# c65Keyb.net
KiCad netlist of a schematic drawn in EAGLE
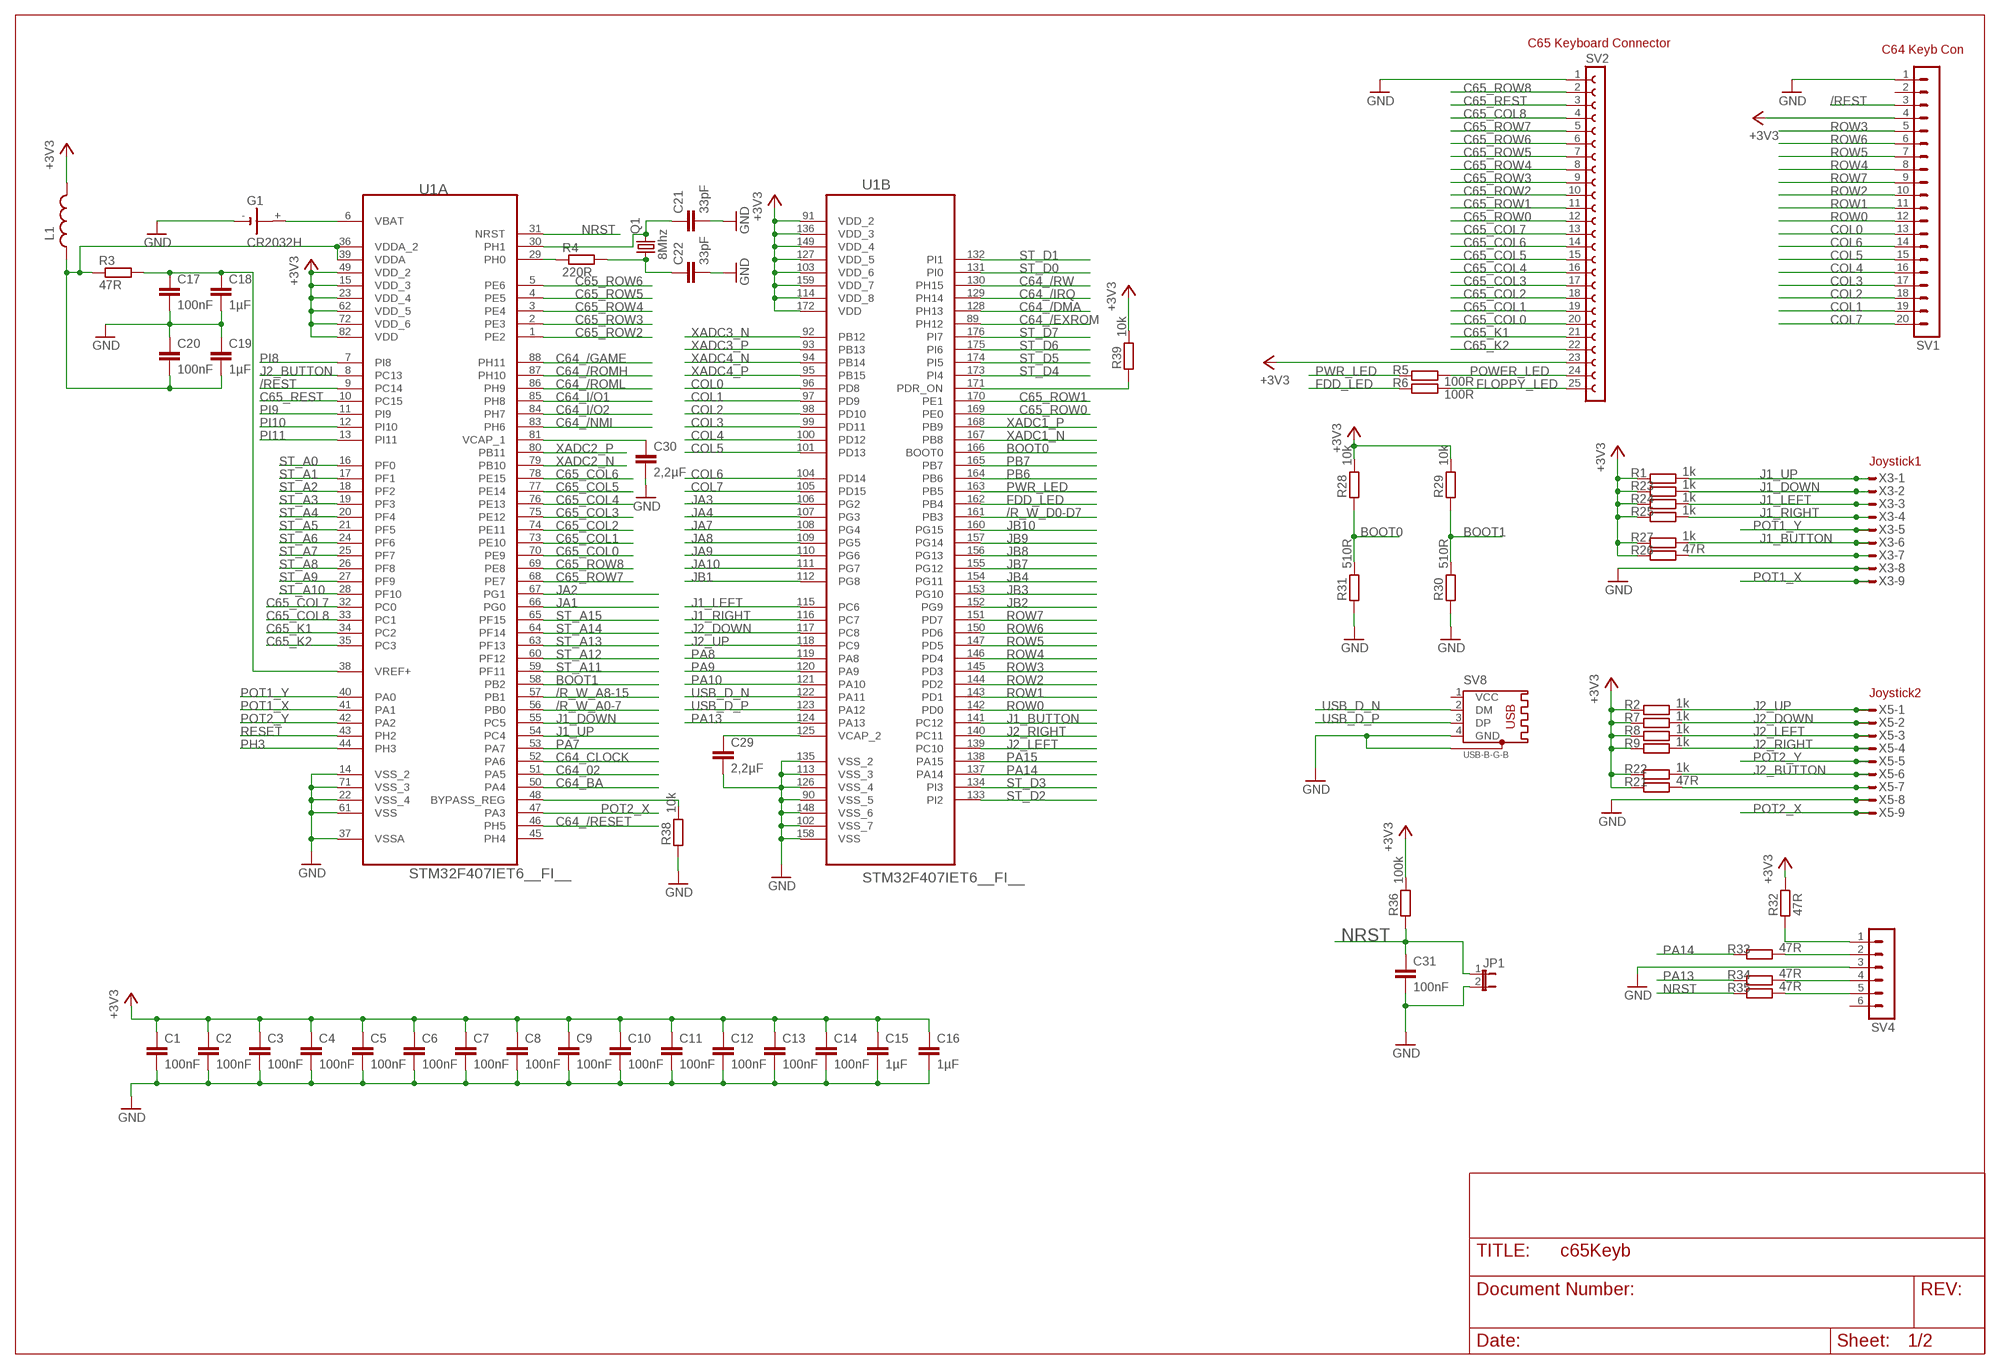
[diagram p0: schematic, sheet 1]
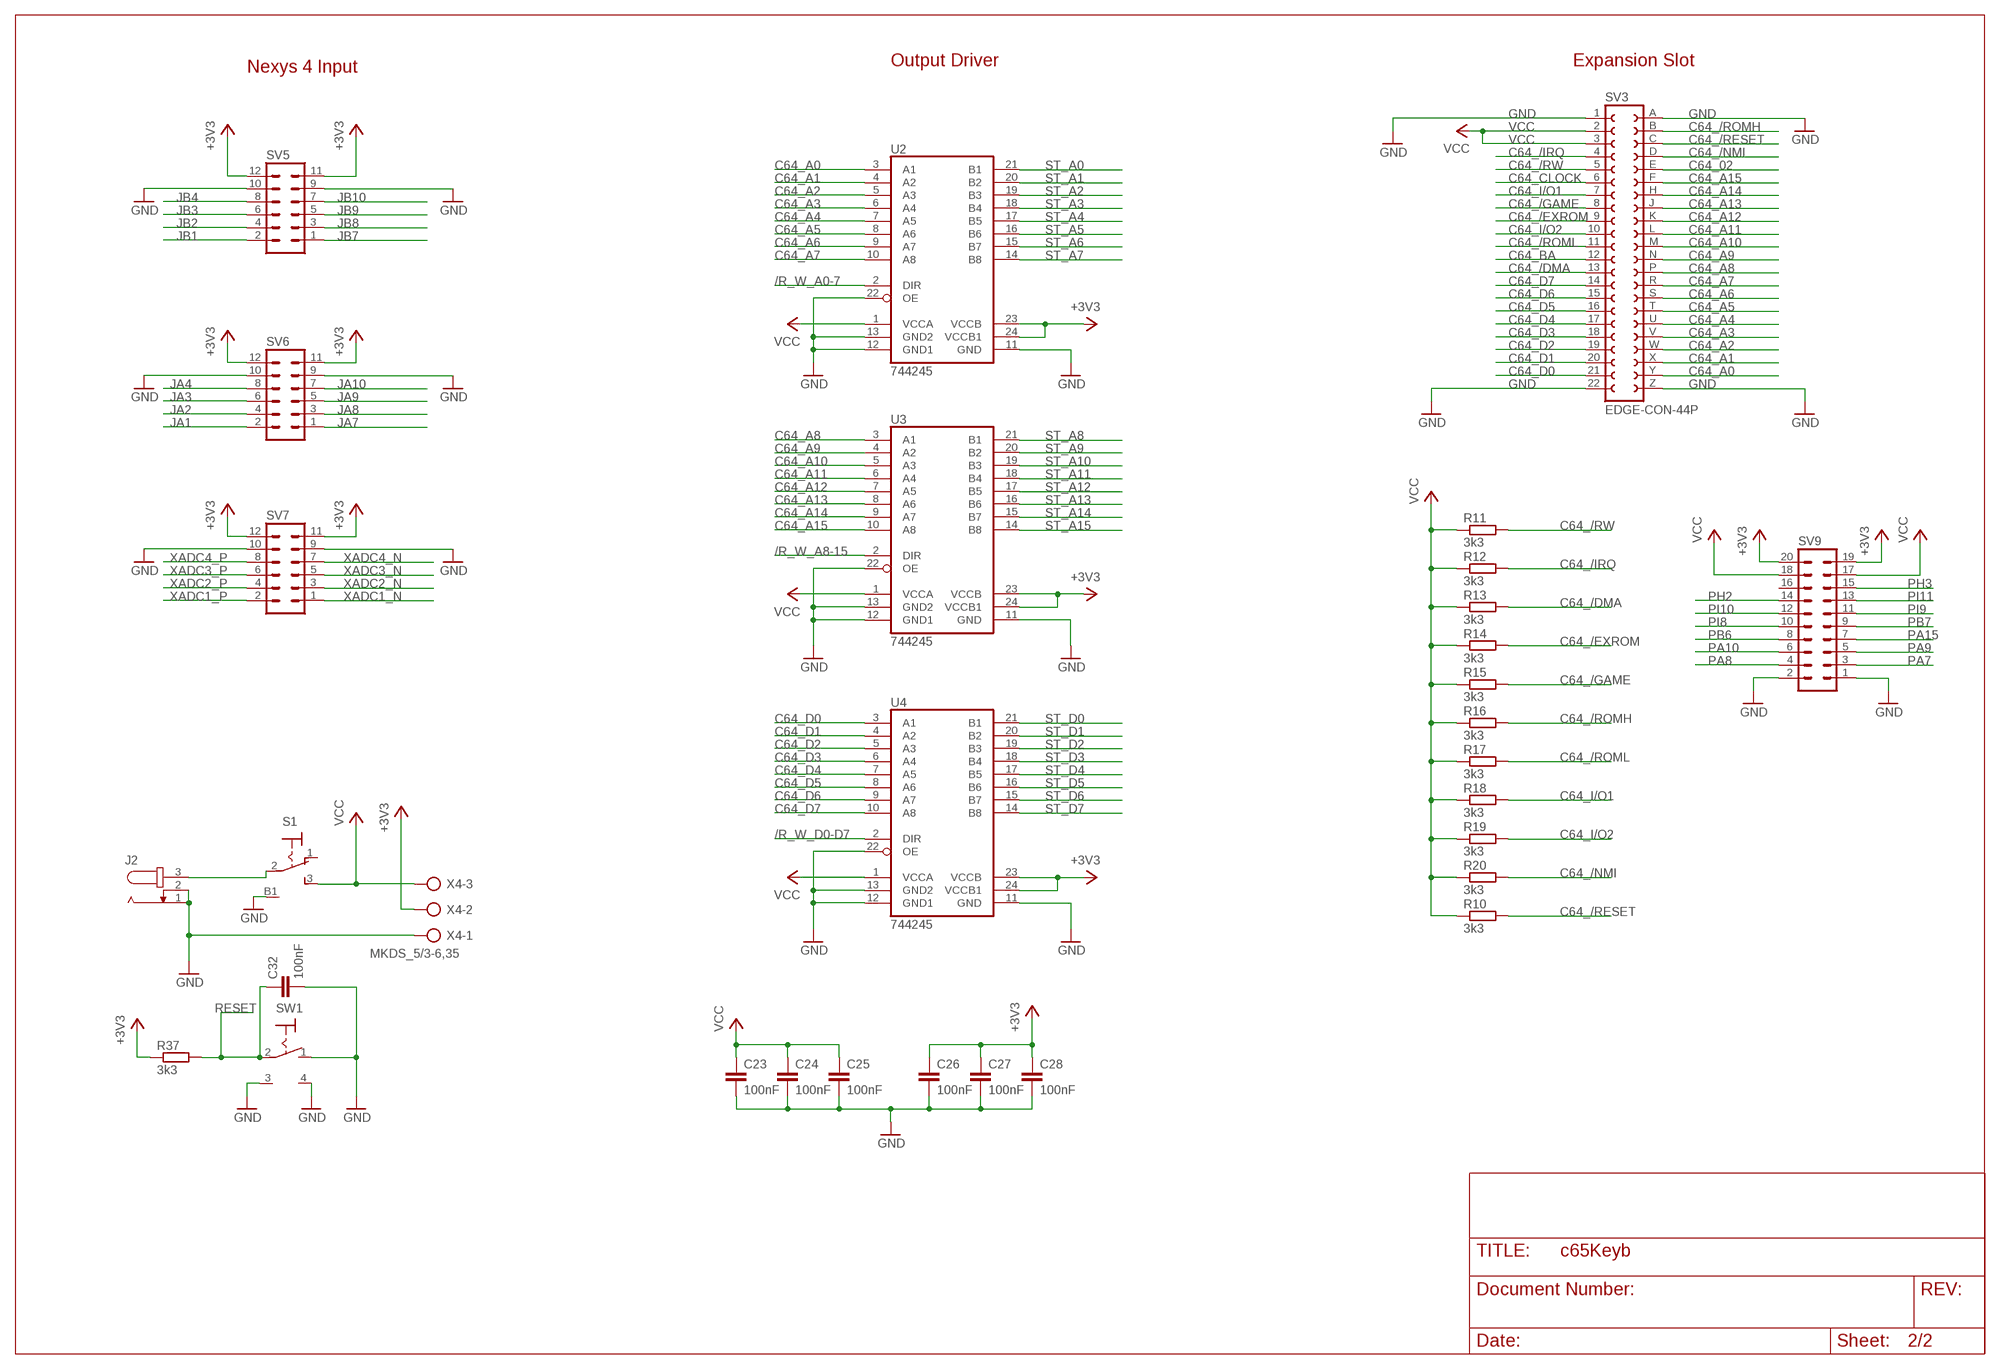
[diagram p1: schematic, sheet 2]

(export (version "E")
  (design (tool "Eeschema 10.0.6"))
  (components
    (comp (ref "C1")
      (value "100nF")
      (footprint "eagle-import:C0805")
      (libsource (lib "eagle-import") (part "C-EUC0805"))
    )
    (comp (ref "C2")
      (value "100nF")
      (footprint "eagle-import:C0805")
      (libsource (lib "eagle-import") (part "C-EUC0805"))
    )
    (comp (ref "C3")
      (value "100nF")
      (footprint "eagle-import:C0805")
      (libsource (lib "eagle-import") (part "C-EUC0805"))
    )
    (comp (ref "C4")
      (value "100nF")
      (footprint "eagle-import:C0805")
      (libsource (lib "eagle-import") (part "C-EUC0805"))
    )
    (comp (ref "C5")
      (value "100nF")
      (footprint "eagle-import:C0805")
      (libsource (lib "eagle-import") (part "C-EUC0805"))
    )
    (comp (ref "C6")
      (value "100nF")
      (footprint "eagle-import:C0805")
      (libsource (lib "eagle-import") (part "C-EUC0805"))
    )
    (comp (ref "C7")
      (value "100nF")
      (footprint "eagle-import:C0805")
      (libsource (lib "eagle-import") (part "C-EUC0805"))
    )
    (comp (ref "C8")
      (value "100nF")
      (footprint "eagle-import:C0805")
      (libsource (lib "eagle-import") (part "C-EUC0805"))
    )
    (comp (ref "C9")
      (value "100nF")
      (footprint "eagle-import:C0805")
      (libsource (lib "eagle-import") (part "C-EUC0805"))
    )
    (comp (ref "C10")
      (value "100nF")
      (footprint "eagle-import:C0805")
      (libsource (lib "eagle-import") (part "C-EUC0805"))
    )
    (comp (ref "C11")
      (value "100nF")
      (footprint "eagle-import:C0805")
      (libsource (lib "eagle-import") (part "C-EUC0805"))
    )
    (comp (ref "C12")
      (value "100nF")
      (footprint "eagle-import:C0805")
      (libsource (lib "eagle-import") (part "C-EUC0805"))
    )
    (comp (ref "C13")
      (value "100nF")
      (footprint "eagle-import:C0805")
      (libsource (lib "eagle-import") (part "C-EUC0805"))
    )
    (comp (ref "C14")
      (value "100nF")
      (footprint "eagle-import:C0805")
      (libsource (lib "eagle-import") (part "C-EUC0805"))
    )
    (comp (ref "C15")
      (value "1µF")
      (footprint "eagle-import:C0805")
      (libsource (lib "eagle-import") (part "C-EUC0805"))
    )
    (comp (ref "C16")
      (value "1µF")
      (footprint "eagle-import:C0805")
      (libsource (lib "eagle-import") (part "C-EUC0805"))
    )
    (comp (ref "C17")
      (value "100nF")
      (footprint "eagle-import:C0805")
      (libsource (lib "eagle-import") (part "C-EUC0805"))
    )
    (comp (ref "C18")
      (value "1µF")
      (footprint "eagle-import:C0805")
      (libsource (lib "eagle-import") (part "C-EUC0805"))
    )
    (comp (ref "C19")
      (value "1µF")
      (footprint "eagle-import:C0805")
      (libsource (lib "eagle-import") (part "C-EUC0805"))
    )
    (comp (ref "C20")
      (value "100nF")
      (footprint "eagle-import:C0805")
      (libsource (lib "eagle-import") (part "C-EUC0805"))
    )
    (comp (ref "C21")
      (value "33pF")
      (footprint "eagle-import:C0805")
      (libsource (lib "eagle-import") (part "C-EUC0805"))
    )
    (comp (ref "C22")
      (value "33pF")
      (footprint "eagle-import:C0805")
      (libsource (lib "eagle-import") (part "C-EUC0805"))
    )
    (comp (ref "C29")
      (value "2,2µF")
      (footprint "eagle-import:C0805")
      (libsource (lib "eagle-import") (part "C-EUC0805"))
    )
    (comp (ref "C30")
      (value "2,2µF")
      (footprint "eagle-import:C0805")
      (libsource (lib "eagle-import") (part "C-EUC0805"))
    )
    (comp (ref "C31")
      (value "100nF")
      (footprint "eagle-import:C0805")
      (libsource (lib "eagle-import") (part "C-EUC0805"))
    )
    (comp (ref "G1")
      (value "CR2032H")
      (footprint "eagle-import:CR2032H")
      (libsource (lib "eagle-import") (part "CR2032H"))
    )
    (comp (ref "JP1")
      (value "JP1E")
      (footprint "eagle-import:JP1")
      (libsource (lib "eagle-import") (part "JP1E"))
    )
    (comp (ref "L1")
      (value "L-0805A")
      (footprint "eagle-import:SMD0805-ALT")
      (libsource (lib "eagle-import") (part "L-0805A"))
    )
    (comp (ref "Q1")
      (value "8Mhz")
      (footprint "eagle-import:HC49UP")
      (libsource (lib "eagle-import") (part "CRYSTAL-HC49UP"))
    )
    (comp (ref "R1")
      (value "1k")
      (footprint "eagle-import:R0805")
      (libsource (lib "eagle-import") (part "R-EU_R0805"))
    )
    (comp (ref "R2")
      (value "1k")
      (footprint "eagle-import:R0805")
      (libsource (lib "eagle-import") (part "R-EU_R0805"))
    )
    (comp (ref "R3")
      (value "47R")
      (footprint "eagle-import:R0805")
      (libsource (lib "eagle-import") (part "R-EU_R0805"))
    )
    (comp (ref "R4")
      (value "220R")
      (footprint "eagle-import:R0805")
      (libsource (lib "eagle-import") (part "R-EU_R0805"))
    )
    (comp (ref "R5")
      (value "100R")
      (footprint "eagle-import:R0805")
      (libsource (lib "eagle-import") (part "R-EU_R0805"))
    )
    (comp (ref "R6")
      (value "100R")
      (footprint "eagle-import:R0805")
      (libsource (lib "eagle-import") (part "R-EU_R0805"))
    )
    (comp (ref "R7")
      (value "1k")
      (footprint "eagle-import:R0805")
      (libsource (lib "eagle-import") (part "R-EU_R0805"))
    )
    (comp (ref "R8")
      (value "1k")
      (footprint "eagle-import:R0805")
      (libsource (lib "eagle-import") (part "R-EU_R0805"))
    )
    (comp (ref "R9")
      (value "1k")
      (footprint "eagle-import:R0805")
      (libsource (lib "eagle-import") (part "R-EU_R0805"))
    )
    (comp (ref "R21")
      (value "47R")
      (footprint "eagle-import:R0805")
      (libsource (lib "eagle-import") (part "R-EU_R0805"))
    )
    (comp (ref "R22")
      (value "1k")
      (footprint "eagle-import:R0805")
      (libsource (lib "eagle-import") (part "R-EU_R0805"))
    )
    (comp (ref "R23")
      (value "1k")
      (footprint "eagle-import:R0805")
      (libsource (lib "eagle-import") (part "R-EU_R0805"))
    )
    (comp (ref "R24")
      (value "1k")
      (footprint "eagle-import:R0805")
      (libsource (lib "eagle-import") (part "R-EU_R0805"))
    )
    (comp (ref "R25")
      (value "1k")
      (footprint "eagle-import:R0805")
      (libsource (lib "eagle-import") (part "R-EU_R0805"))
    )
    (comp (ref "R26")
      (value "47R")
      (footprint "eagle-import:R0805")
      (libsource (lib "eagle-import") (part "R-EU_R0805"))
    )
    (comp (ref "R27")
      (value "1k")
      (footprint "eagle-import:R0805")
      (libsource (lib "eagle-import") (part "R-EU_R0805"))
    )
    (comp (ref "R28")
      (value "10k")
      (footprint "eagle-import:R0805")
      (libsource (lib "eagle-import") (part "R-EU_R0805"))
    )
    (comp (ref "R29")
      (value "10k")
      (footprint "eagle-import:R0805")
      (libsource (lib "eagle-import") (part "R-EU_R0805"))
    )
    (comp (ref "R30")
      (value "510R")
      (footprint "eagle-import:R0805")
      (libsource (lib "eagle-import") (part "R-EU_R0805"))
    )
    (comp (ref "R31")
      (value "510R")
      (footprint "eagle-import:R0805")
      (libsource (lib "eagle-import") (part "R-EU_R0805"))
    )
    (comp (ref "R32")
      (value "47R")
      (footprint "eagle-import:R0805")
      (libsource (lib "eagle-import") (part "R-EU_R0805"))
    )
    (comp (ref "R33")
      (value "47R")
      (footprint "eagle-import:R0805")
      (libsource (lib "eagle-import") (part "R-EU_R0805"))
    )
    (comp (ref "R34")
      (value "47R")
      (footprint "eagle-import:R0805")
      (libsource (lib "eagle-import") (part "R-EU_R0805"))
    )
    (comp (ref "R35")
      (value "47R")
      (footprint "eagle-import:R0805")
      (libsource (lib "eagle-import") (part "R-EU_R0805"))
    )
    (comp (ref "R36")
      (value "100k")
      (footprint "eagle-import:R0805")
      (libsource (lib "eagle-import") (part "R-EU_R0805"))
    )
    (comp (ref "R38")
      (value "10k")
      (footprint "eagle-import:R0805")
      (libsource (lib "eagle-import") (part "R-EU_R0805"))
    )
    (comp (ref "R39")
      (value "10k")
      (footprint "eagle-import:R0805")
      (libsource (lib "eagle-import") (part "R-EU_R0805"))
    )
    (comp (ref "SV1")
      (value "MA20-1")
      (footprint "eagle-import:MA20-1")
      (libsource (lib "eagle-import") (part "MA20-1"))
    )
    (comp (ref "SV2")
      (value "C65_MOLEX_KEYB")
      (footprint "eagle-import:C65_MOLEX_KEYB")
      (libsource (lib "eagle-import") (part "C65_MOLEX_KEYB"))
    )
    (comp (ref "SV4")
      (value "MA06-1")
      (footprint "eagle-import:MA06-1")
      (libsource (lib "eagle-import") (part "MA06-1"))
    )
    (comp (ref "SV8")
      (value "USB-B-G-B")
      (footprint "eagle-import:USB-B-THG-01")
      (libsource (lib "eagle-import") (part "USB-B-G-B"))
    )
    (comp (ref "U1")
      (value "STM32F407IET6__FI__")
      (footprint "eagle-import:QFP176")
      (libsource (lib "eagle-import") (part "STM32F407IET6__FI__"))
    )
    (comp (ref "X3")
      (value "M09-182S")
      (footprint "eagle-import:182-009-MALE")
      (libsource (lib "eagle-import") (part "M09?S-182"))
    )
    (comp (ref "X5")
      (value "M09-182S")
      (footprint "eagle-import:182-009-MALE")
      (libsource (lib "eagle-import") (part "M09?S-182"))
    )
    (comp (ref "C23")
      (value "100nF")
      (footprint "eagle-import:C0805")
      (libsource (lib "eagle-import") (part "C-EUC0805"))
    )
    (comp (ref "C24")
      (value "100nF")
      (footprint "eagle-import:C0805")
      (libsource (lib "eagle-import") (part "C-EUC0805"))
    )
    (comp (ref "C25")
      (value "100nF")
      (footprint "eagle-import:C0805")
      (libsource (lib "eagle-import") (part "C-EUC0805"))
    )
    (comp (ref "C26")
      (value "100nF")
      (footprint "eagle-import:C0805")
      (libsource (lib "eagle-import") (part "C-EUC0805"))
    )
    (comp (ref "C27")
      (value "100nF")
      (footprint "eagle-import:C0805")
      (libsource (lib "eagle-import") (part "C-EUC0805"))
    )
    (comp (ref "C28")
      (value "100nF")
      (footprint "eagle-import:C0805")
      (libsource (lib "eagle-import") (part "C-EUC0805"))
    )
    (comp (ref "C32")
      (value "100nF")
      (footprint "eagle-import:C0805")
      (libsource (lib "eagle-import") (part "C-EUC0805"))
    )
    (comp (ref "J2")
      (value "JACK-PLUG1")
      (footprint "eagle-import:SPC4078")
      (libsource (lib "eagle-import") (part "JACK-PLUG1"))
    )
    (comp (ref "R10")
      (value "3k3")
      (footprint "eagle-import:R0805")
      (libsource (lib "eagle-import") (part "R-EU_R0805"))
    )
    (comp (ref "R11")
      (value "3k3")
      (footprint "eagle-import:R0805")
      (libsource (lib "eagle-import") (part "R-EU_R0805"))
    )
    (comp (ref "R12")
      (value "3k3")
      (footprint "eagle-import:R0805")
      (libsource (lib "eagle-import") (part "R-EU_R0805"))
    )
    (comp (ref "R13")
      (value "3k3")
      (footprint "eagle-import:R0805")
      (libsource (lib "eagle-import") (part "R-EU_R0805"))
    )
    (comp (ref "R14")
      (value "3k3")
      (footprint "eagle-import:R0805")
      (libsource (lib "eagle-import") (part "R-EU_R0805"))
    )
    (comp (ref "R15")
      (value "3k3")
      (footprint "eagle-import:R0805")
      (libsource (lib "eagle-import") (part "R-EU_R0805"))
    )
    (comp (ref "R16")
      (value "3k3")
      (footprint "eagle-import:R0805")
      (libsource (lib "eagle-import") (part "R-EU_R0805"))
    )
    (comp (ref "R17")
      (value "3k3")
      (footprint "eagle-import:R0805")
      (libsource (lib "eagle-import") (part "R-EU_R0805"))
    )
    (comp (ref "R18")
      (value "3k3")
      (footprint "eagle-import:R0805")
      (libsource (lib "eagle-import") (part "R-EU_R0805"))
    )
    (comp (ref "R19")
      (value "3k3")
      (footprint "eagle-import:R0805")
      (libsource (lib "eagle-import") (part "R-EU_R0805"))
    )
    (comp (ref "R20")
      (value "3k3")
      (footprint "eagle-import:R0805")
      (libsource (lib "eagle-import") (part "R-EU_R0805"))
    )
    (comp (ref "R37")
      (value "3k3")
      (footprint "eagle-import:R0805")
      (libsource (lib "eagle-import") (part "R-EU_R0805"))
    )
    (comp (ref "S1")
      (value "LPV-1")
      (footprint "eagle-import:LPV-1")
      (libsource (lib "eagle-import") (part "LPV-1"))
    )
    (comp (ref "SV3")
      (value "EDGE-CON-44P")
      (footprint "eagle-import:EDGE-CON-44")
      (libsource (lib "eagle-import") (part "EDGE-CON-44P"))
    )
    (comp (ref "SV5")
      (value "MA06-2W")
      (footprint "eagle-import:MA06-2W")
      (libsource (lib "eagle-import") (part "MA06-2W"))
    )
    (comp (ref "SV6")
      (value "MA06-2W")
      (footprint "eagle-import:MA06-2W")
      (libsource (lib "eagle-import") (part "MA06-2W"))
    )
    (comp (ref "SV7")
      (value "MA06-2W")
      (footprint "eagle-import:MA06-2W")
      (libsource (lib "eagle-import") (part "MA06-2W"))
    )
    (comp (ref "SV9")
      (value "MA10-2")
      (footprint "eagle-import:MA10-2")
      (libsource (lib "eagle-import") (part "MA10-2"))
    )
    (comp (ref "SW1")
      (value "TASTER")
      (footprint "eagle-import:MICRO_SWITCH")
      (libsource (lib "eagle-import") (part "TASTER"))
    )
    (comp (ref "U2")
      (value "744245")
      (footprint "eagle-import:SO24L")
      (libsource (lib "eagle-import") (part "744245"))
    )
    (comp (ref "U3")
      (value "744245")
      (footprint "eagle-import:SO24L")
      (libsource (lib "eagle-import") (part "744245"))
    )
    (comp (ref "U4")
      (value "744245")
      (footprint "eagle-import:SO24L")
      (libsource (lib "eagle-import") (part "744245"))
    )
    (comp (ref "X4")
      (value "MKDS_5/3-6,35")
      (footprint "eagle-import:MKDS_5_3-635")
      (fields (field (name "MF") "FARNELL") (field (name "MPN") "1714968"))
      (libsource (lib "eagle-import") (part "MKDS_5/3-6,35"))
    )
  )
  (nets
    (net (code "1") (name "+3V3") (class "Default")
      (node (ref "C1") (pin "1") (pinfunction "1_1") (pintype "passive"))
      (node (ref "C10") (pin "1") (pinfunction "1_1") (pintype "passive"))
      (node (ref "C11") (pin "1") (pinfunction "1_1") (pintype "passive"))
      (node (ref "C12") (pin "1") (pinfunction "1_1") (pintype "passive"))
      (node (ref "C13") (pin "1") (pinfunction "1_1") (pintype "passive"))
      (node (ref "C14") (pin "1") (pinfunction "1_1") (pintype "passive"))
      (node (ref "C15") (pin "1") (pinfunction "1_1") (pintype "passive"))
      (node (ref "C16") (pin "1") (pinfunction "1_1") (pintype "passive"))
      (node (ref "C2") (pin "1") (pinfunction "1_1") (pintype "passive"))
      (node (ref "C26") (pin "1") (pinfunction "1_1") (pintype "passive"))
      (node (ref "C27") (pin "1") (pinfunction "1_1") (pintype "passive"))
      (node (ref "C28") (pin "1") (pinfunction "1_1") (pintype "passive"))
      (node (ref "C3") (pin "1") (pinfunction "1_1") (pintype "passive"))
      (node (ref "C4") (pin "1") (pinfunction "1_1") (pintype "passive"))
      (node (ref "C5") (pin "1") (pinfunction "1_1") (pintype "passive"))
      (node (ref "C6") (pin "1") (pinfunction "1_1") (pintype "passive"))
      (node (ref "C7") (pin "1") (pinfunction "1_1") (pintype "passive"))
      (node (ref "C8") (pin "1") (pinfunction "1_1") (pintype "passive"))
      (node (ref "C9") (pin "1") (pinfunction "1_1") (pintype "passive"))
      (node (ref "L1") (pin "2") (pinfunction "2_2") (pintype "passive"))
      (node (ref "R1") (pin "1") (pinfunction "1_1") (pintype "passive"))
      (node (ref "R2") (pin "1") (pinfunction "1_1") (pintype "passive"))
      (node (ref "R21") (pin "1") (pinfunction "1_1") (pintype "passive"))
      (node (ref "R22") (pin "1") (pinfunction "1_1") (pintype "passive"))
      (node (ref "R23") (pin "1") (pinfunction "1_1") (pintype "passive"))
      (node (ref "R24") (pin "1") (pinfunction "1_1") (pintype "passive"))
      (node (ref "R25") (pin "1") (pinfunction "1_1") (pintype "passive"))
      (node (ref "R26") (pin "1") (pinfunction "1_1") (pintype "passive"))
      (node (ref "R27") (pin "1") (pinfunction "1_1") (pintype "passive"))
      (node (ref "R28") (pin "2") (pinfunction "2_2") (pintype "passive"))
      (node (ref "R29") (pin "2") (pinfunction "2_2") (pintype "passive"))
      (node (ref "R32") (pin "2") (pinfunction "2_2") (pintype "passive"))
      (node (ref "R36") (pin "2") (pinfunction "2_2") (pintype "passive"))
      (node (ref "R37") (pin "1") (pinfunction "1_1") (pintype "passive"))
      (node (ref "R39") (pin "2") (pinfunction "2_2") (pintype "passive"))
      (node (ref "R7") (pin "1") (pinfunction "1_1") (pintype "passive"))
      (node (ref "R8") (pin "1") (pinfunction "1_1") (pintype "passive"))
      (node (ref "R9") (pin "1") (pinfunction "1_1") (pintype "passive"))
      (node (ref "SV1") (pin "4") (pinfunction "4_4") (pintype "passive"))
      (node (ref "SV2") (pin "23") (pinfunction "P23_23") (pintype "passive"))
      (node (ref "SV5") (pin "11") (pinfunction "11_11") (pintype "passive"))
      (node (ref "SV5") (pin "12") (pinfunction "12_12") (pintype "passive"))
      (node (ref "SV6") (pin "11") (pinfunction "11_11") (pintype "passive"))
      (node (ref "SV6") (pin "12") (pinfunction "12_12") (pintype "passive"))
      (node (ref "SV7") (pin "11") (pinfunction "11_11") (pintype "passive"))
      (node (ref "SV7") (pin "12") (pinfunction "12_12") (pintype "passive"))
      (node (ref "SV9") (pin "19") (pinfunction "19_19") (pintype "passive"))
      (node (ref "SV9") (pin "20") (pinfunction "20_20") (pintype "passive"))
      (node (ref "U1") (pin "103") (pinfunction "VDD_6_103") (pintype "power_in"))
      (node (ref "U1") (pin "114") (pinfunction "VDD_8_114") (pintype "power_in"))
      (node (ref "U1") (pin "127") (pinfunction "VDD_5_127") (pintype "power_in"))
      (node (ref "U1") (pin "136") (pinfunction "VDD_3_136") (pintype "power_in"))
      (node (ref "U1") (pin "149") (pinfunction "VDD_4_149") (pintype "power_in"))
      (node (ref "U1") (pin "15") (pinfunction "VDD_3_15") (pintype "power_in"))
      (node (ref "U1") (pin "159") (pinfunction "VDD_7_159") (pintype "power_in"))
      (node (ref "U1") (pin "172") (pinfunction "VDD_172") (pintype "power_in"))
      (node (ref "U1") (pin "23") (pinfunction "VDD_4_23") (pintype "power_in"))
      (node (ref "U1") (pin "49") (pinfunction "VDD_2_49") (pintype "power_in"))
      (node (ref "U1") (pin "62") (pinfunction "VDD_5_62") (pintype "power_in"))
      (node (ref "U1") (pin "72") (pinfunction "VDD_6_72") (pintype "power_in"))
      (node (ref "U1") (pin "82") (pinfunction "VDD_82") (pintype "power_in"))
      (node (ref "U1") (pin "91") (pinfunction "VDD_2_91") (pintype "power_in"))
      (node (ref "U2") (pin "23") (pinfunction "VCCB_23") (pintype "power_in"))
      (node (ref "U2") (pin "24") (pinfunction "VCCB1_24") (pintype "power_in"))
      (node (ref "U3") (pin "23") (pinfunction "VCCB_23") (pintype "power_in"))
      (node (ref "U3") (pin "24") (pinfunction "VCCB1_24") (pintype "power_in"))
      (node (ref "U4") (pin "23") (pinfunction "VCCB_23") (pintype "power_in"))
      (node (ref "U4") (pin "24") (pinfunction "VCCB1_24") (pintype "power_in"))
      (node (ref "X4") (pin "2") (pinfunction "KL_2") (pintype "passive"))
    )
    (net (code "2") (name "BOOT0") (class "Default")
      (node (ref "R28") (pin "1") (pinfunction "1_1") (pintype "passive"))
      (node (ref "R31") (pin "2") (pinfunction "2_2") (pintype "passive"))
      (node (ref "U1") (pin "166") (pinfunction "BOOT0_166") (pintype "passive"))
    )
    (net (code "3") (name "BOOT1") (class "Default")
      (node (ref "R29") (pin "1") (pinfunction "1_1") (pintype "passive"))
      (node (ref "R30") (pin "2") (pinfunction "2_2") (pintype "passive"))
      (node (ref "U1") (pin "58") (pinfunction "PB2_58") (pintype "bidirectional"))
    )
    (net (code "4") (name "C64_02") (class "Default")
      (node (ref "SV3") (pin "E") (pinfunction "E_E") (pintype "passive"))
      (node (ref "U1") (pin "51") (pinfunction "PA5_51") (pintype "passive"))
    )
    (net (code "5") (name "C64_A0") (class "Default")
      (node (ref "SV3") (pin "Y") (pinfunction "Y_Y") (pintype "passive"))
      (node (ref "U2") (pin "3") (pinfunction "A1_3") (pintype "bidirectional"))
    )
    (net (code "6") (name "C64_A1") (class "Default")
      (node (ref "SV3") (pin "X") (pinfunction "X_X") (pintype "passive"))
      (node (ref "U2") (pin "4") (pinfunction "A2_4") (pintype "bidirectional"))
    )
    (net (code "7") (name "C64_A2") (class "Default")
      (node (ref "SV3") (pin "W") (pinfunction "W_W") (pintype "passive"))
      (node (ref "U2") (pin "5") (pinfunction "A3_5") (pintype "bidirectional"))
    )
    (net (code "8") (name "C64_A3") (class "Default")
      (node (ref "SV3") (pin "V") (pinfunction "V_V") (pintype "passive"))
      (node (ref "U2") (pin "6") (pinfunction "A4_6") (pintype "bidirectional"))
    )
    (net (code "9") (name "C64_A4") (class "Default")
      (node (ref "SV3") (pin "U") (pinfunction "U_U") (pintype "passive"))
      (node (ref "U2") (pin "7") (pinfunction "A5_7") (pintype "bidirectional"))
    )
    (net (code "10") (name "C64_A5") (class "Default")
      (node (ref "SV3") (pin "T") (pinfunction "T_T") (pintype "passive"))
      (node (ref "U2") (pin "8") (pinfunction "A6_8") (pintype "bidirectional"))
    )
    (net (code "11") (name "C64_A6") (class "Default")
      (node (ref "SV3") (pin "S") (pinfunction "S_S") (pintype "passive"))
      (node (ref "U2") (pin "9") (pinfunction "A7_9") (pintype "bidirectional"))
    )
    (net (code "12") (name "C64_A7") (class "Default")
      (node (ref "SV3") (pin "R") (pinfunction "R_R") (pintype "passive"))
      (node (ref "U2") (pin "10") (pinfunction "A8_10") (pintype "bidirectional"))
    )
    (net (code "13") (name "C64_A8") (class "Default")
      (node (ref "SV3") (pin "P") (pinfunction "P_P") (pintype "passive"))
      (node (ref "U3") (pin "3") (pinfunction "A1_3") (pintype "bidirectional"))
    )
    (net (code "14") (name "C64_A9") (class "Default")
      (node (ref "SV3") (pin "N") (pinfunction "N_N") (pintype "passive"))
      (node (ref "U3") (pin "4") (pinfunction "A2_4") (pintype "bidirectional"))
    )
    (net (code "15") (name "C64_A10") (class "Default")
      (node (ref "SV3") (pin "M") (pinfunction "M_M") (pintype "passive"))
      (node (ref "U3") (pin "5") (pinfunction "A3_5") (pintype "bidirectional"))
    )
    (net (code "16") (name "C64_A11") (class "Default")
      (node (ref "SV3") (pin "L") (pinfunction "L_L") (pintype "passive"))
      (node (ref "U3") (pin "6") (pinfunction "A4_6") (pintype "bidirectional"))
    )
    (net (code "17") (name "C64_A12") (class "Default")
      (node (ref "SV3") (pin "K") (pinfunction "K_K") (pintype "passive"))
      (node (ref "U3") (pin "7") (pinfunction "A5_7") (pintype "bidirectional"))
    )
    (net (code "18") (name "C64_A13") (class "Default")
      (node (ref "SV3") (pin "J") (pinfunction "J_J") (pintype "passive"))
      (node (ref "U3") (pin "8") (pinfunction "A6_8") (pintype "bidirectional"))
    )
    (net (code "19") (name "C64_A14") (class "Default")
      (node (ref "SV3") (pin "H") (pinfunction "H_H") (pintype "passive"))
      (node (ref "U3") (pin "9") (pinfunction "A7_9") (pintype "bidirectional"))
    )
    (net (code "20") (name "C64_A15") (class "Default")
      (node (ref "SV3") (pin "F") (pinfunction "F_F") (pintype "passive"))
      (node (ref "U3") (pin "10") (pinfunction "A8_10") (pintype "bidirectional"))
    )
    (net (code "21") (name "C64_BA") (class "Default")
      (node (ref "SV3") (pin "12") (pinfunction "12_12") (pintype "passive"))
      (node (ref "U1") (pin "50") (pinfunction "PA4_50") (pintype "passive"))
    )
    (net (code "22") (name "C64_CLOCK") (class "Default")
      (node (ref "SV3") (pin "6") (pinfunction "6_6") (pintype "passive"))
      (node (ref "U1") (pin "52") (pinfunction "PA6_52") (pintype "passive"))
    )
    (net (code "23") (name "C64_D0") (class "Default")
      (node (ref "SV3") (pin "21") (pinfunction "21_21") (pintype "passive"))
      (node (ref "U4") (pin "3") (pinfunction "A1_3") (pintype "bidirectional"))
    )
    (net (code "24") (name "C64_D1") (class "Default")
      (node (ref "SV3") (pin "20") (pinfunction "20_20") (pintype "passive"))
      (node (ref "U4") (pin "4") (pinfunction "A2_4") (pintype "bidirectional"))
    )
    (net (code "25") (name "C64_D2") (class "Default")
      (node (ref "SV3") (pin "19") (pinfunction "19_19") (pintype "passive"))
      (node (ref "U4") (pin "5") (pinfunction "A3_5") (pintype "bidirectional"))
    )
    (net (code "26") (name "C64_D3") (class "Default")
      (node (ref "SV3") (pin "18") (pinfunction "18_18") (pintype "passive"))
      (node (ref "U4") (pin "6") (pinfunction "A4_6") (pintype "bidirectional"))
    )
    (net (code "27") (name "C64_D4") (class "Default")
      (node (ref "SV3") (pin "17") (pinfunction "17_17") (pintype "passive"))
      (node (ref "U4") (pin "7") (pinfunction "A5_7") (pintype "bidirectional"))
    )
    (net (code "28") (name "C64_D5") (class "Default")
      (node (ref "SV3") (pin "16") (pinfunction "16_16") (pintype "passive"))
      (node (ref "U4") (pin "8") (pinfunction "A6_8") (pintype "bidirectional"))
    )
    (net (code "29") (name "C64_D6") (class "Default")
      (node (ref "SV3") (pin "15") (pinfunction "15_15") (pintype "passive"))
      (node (ref "U4") (pin "9") (pinfunction "A7_9") (pintype "bidirectional"))
    )
    (net (code "30") (name "C64_D7") (class "Default")
      (node (ref "SV3") (pin "14") (pinfunction "14_14") (pintype "passive"))
      (node (ref "U4") (pin "10") (pinfunction "A8_10") (pintype "bidirectional"))
    )
    (net (code "31") (name "C64_I{slash}O1") (class "Default")
      (node (ref "R18") (pin "2") (pinfunction "2_2") (pintype "passive"))
      (node (ref "SV3") (pin "7") (pinfunction "7_7") (pintype "passive"))
      (node (ref "U1") (pin "85") (pinfunction "PH8_85") (pintype "bidirectional"))
    )
    (net (code "32") (name "C64_I{slash}O2") (class "Default")
      (node (ref "R19") (pin "2") (pinfunction "2_2") (pintype "passive"))
      (node (ref "SV3") (pin "10") (pinfunction "10_10") (pintype "passive"))
      (node (ref "U1") (pin "84") (pinfunction "PH7_84") (pintype "bidirectional"))
    )
    (net (code "33") (name "C64_{slash}DMA") (class "Default")
      (node (ref "R13") (pin "2") (pinfunction "2_2") (pintype "passive"))
      (node (ref "SV3") (pin "13") (pinfunction "13_13") (pintype "passive"))
      (node (ref "U1") (pin "128") (pinfunction "PH13_128") (pintype "bidirectional"))
    )
    (net (code "34") (name "C64_{slash}EXROM") (class "Default")
      (node (ref "R14") (pin "2") (pinfunction "2_2") (pintype "passive"))
      (node (ref "SV3") (pin "9") (pinfunction "9_9") (pintype "passive"))
      (node (ref "U1") (pin "89") (pinfunction "PH12_89") (pintype "bidirectional"))
    )
    (net (code "35") (name "C64_{slash}GAME") (class "Default")
      (node (ref "R15") (pin "2") (pinfunction "2_2") (pintype "passive"))
      (node (ref "SV3") (pin "8") (pinfunction "8_8") (pintype "passive"))
      (node (ref "U1") (pin "88") (pinfunction "PH11_88") (pintype "bidirectional"))
    )
    (net (code "36") (name "C64_{slash}IRQ") (class "Default")
      (node (ref "R12") (pin "2") (pinfunction "2_2") (pintype "passive"))
      (node (ref "SV3") (pin "4") (pinfunction "4_4") (pintype "passive"))
      (node (ref "U1") (pin "129") (pinfunction "PH14_129") (pintype "bidirectional"))
    )
    (net (code "37") (name "C64_{slash}NMI") (class "Default")
      (node (ref "R20") (pin "2") (pinfunction "2_2") (pintype "passive"))
      (node (ref "SV3") (pin "D") (pinfunction "D_D") (pintype "passive"))
      (node (ref "U1") (pin "83") (pinfunction "PH6_83") (pintype "bidirectional"))
    )
    (net (code "38") (name "C64_{slash}RESET") (class "Default")
      (node (ref "R10") (pin "2") (pinfunction "2_2") (pintype "passive"))
      (node (ref "SV3") (pin "C") (pinfunction "C_C") (pintype "passive"))
      (node (ref "U1") (pin "46") (pinfunction "PH5_46") (pintype "passive"))
    )
    (net (code "39") (name "C64_{slash}ROMH") (class "Default")
      (node (ref "R16") (pin "2") (pinfunction "2_2") (pintype "passive"))
      (node (ref "SV3") (pin "B") (pinfunction "B_B") (pintype "passive"))
      (node (ref "U1") (pin "87") (pinfunction "PH10_87") (pintype "bidirectional"))
    )
    (net (code "40") (name "C64_{slash}ROML") (class "Default")
      (node (ref "R17") (pin "2") (pinfunction "2_2") (pintype "passive"))
      (node (ref "SV3") (pin "11") (pinfunction "11_11") (pintype "passive"))
      (node (ref "U1") (pin "86") (pinfunction "PH9_86") (pintype "bidirectional"))
    )
    (net (code "41") (name "C64_{slash}RW") (class "Default")
      (node (ref "R11") (pin "2") (pinfunction "2_2") (pintype "passive"))
      (node (ref "SV3") (pin "5") (pinfunction "5_5") (pintype "passive"))
      (node (ref "U1") (pin "130") (pinfunction "PH15_130") (pintype "bidirectional"))
    )
    (net (code "42") (name "C65_COL0") (class "Default")
      (node (ref "SV2") (pin "20") (pinfunction "P20_20") (pintype "passive"))
      (node (ref "U1") (pin "70") (pinfunction "PE9_70") (pintype "bidirectional"))
    )
    (net (code "43") (name "C65_COL1") (class "Default")
      (node (ref "SV2") (pin "19") (pinfunction "P19_19") (pintype "passive"))
      (node (ref "U1") (pin "73") (pinfunction "PE10_73") (pintype "bidirectional"))
    )
    (net (code "44") (name "C65_COL2") (class "Default")
      (node (ref "SV2") (pin "18") (pinfunction "P18_18") (pintype "passive"))
      (node (ref "U1") (pin "74") (pinfunction "PE11_74") (pintype "bidirectional"))
    )
    (net (code "45") (name "C65_COL3") (class "Default")
      (node (ref "SV2") (pin "17") (pinfunction "P17_17") (pintype "passive"))
      (node (ref "U1") (pin "75") (pinfunction "PE12_75") (pintype "bidirectional"))
    )
    (net (code "46") (name "C65_COL4") (class "Default")
      (node (ref "SV2") (pin "16") (pinfunction "P16_16") (pintype "passive"))
      (node (ref "U1") (pin "76") (pinfunction "PE13_76") (pintype "bidirectional"))
    )
    (net (code "47") (name "C65_COL5") (class "Default")
      (node (ref "SV2") (pin "15") (pinfunction "P15_15") (pintype "passive"))
      (node (ref "U1") (pin "77") (pinfunction "PE14_77") (pintype "bidirectional"))
    )
    (net (code "48") (name "C65_COL6") (class "Default")
      (node (ref "SV2") (pin "14") (pinfunction "P14_14") (pintype "passive"))
      (node (ref "U1") (pin "78") (pinfunction "PE15_78") (pintype "bidirectional"))
    )
    (net (code "49") (name "C65_COL7") (class "Default")
      (node (ref "SV2") (pin "13") (pinfunction "P13_13") (pintype "passive"))
      (node (ref "U1") (pin "32") (pinfunction "PC0_32") (pintype "passive"))
    )
    (net (code "50") (name "C65_COL8") (class "Default")
      (node (ref "SV2") (pin "4") (pinfunction "P4_4") (pintype "passive"))
      (node (ref "U1") (pin "33") (pinfunction "PC1_33") (pintype "passive"))
    )
    (net (code "51") (name "C65_K1") (class "Default")
      (node (ref "SV2") (pin "21") (pinfunction "P21_21") (pintype "passive"))
      (node (ref "U1") (pin "34") (pinfunction "PC2_34") (pintype "passive"))
    )
    (net (code "52") (name "C65_K2") (class "Default")
      (node (ref "SV2") (pin "22") (pinfunction "P22_22") (pintype "passive"))
      (node (ref "U1") (pin "35") (pinfunction "PC3_35") (pintype "passive"))
    )
    (net (code "53") (name "C65_REST") (class "Default")
      (node (ref "SV2") (pin "3") (pinfunction "P3_3") (pintype "passive"))
      (node (ref "U1") (pin "10") (pinfunction "PC15_10") (pintype "passive"))
    )
    (net (code "54") (name "C65_ROW0") (class "Default")
      (node (ref "SV2") (pin "12") (pinfunction "P12_12") (pintype "passive"))
      (node (ref "U1") (pin "169") (pinfunction "PE0_169") (pintype "bidirectional"))
    )
    (net (code "55") (name "C65_ROW1") (class "Default")
      (node (ref "SV2") (pin "11") (pinfunction "P11_11") (pintype "passive"))
      (node (ref "U1") (pin "170") (pinfunction "PE1_170") (pintype "bidirectional"))
    )
    (net (code "56") (name "C65_ROW2") (class "Default")
      (node (ref "SV2") (pin "10") (pinfunction "P10_10") (pintype "passive"))
      (node (ref "U1") (pin "1") (pinfunction "PE2_1") (pintype "passive"))
    )
    (net (code "57") (name "C65_ROW3") (class "Default")
      (node (ref "SV2") (pin "9") (pinfunction "P9_9") (pintype "passive"))
      (node (ref "U1") (pin "2") (pinfunction "PE3_2") (pintype "passive"))
    )
    (net (code "58") (name "C65_ROW4") (class "Default")
      (node (ref "SV2") (pin "8") (pinfunction "P8_8") (pintype "passive"))
      (node (ref "U1") (pin "3") (pinfunction "PE4_3") (pintype "passive"))
    )
    (net (code "59") (name "C65_ROW5") (class "Default")
      (node (ref "SV2") (pin "7") (pinfunction "P7_7") (pintype "passive"))
      (node (ref "U1") (pin "4") (pinfunction "PE5_4") (pintype "passive"))
    )
    (net (code "60") (name "C65_ROW6") (class "Default")
      (node (ref "SV2") (pin "6") (pinfunction "P6_6") (pintype "passive"))
      (node (ref "U1") (pin "5") (pinfunction "PE6_5") (pintype "passive"))
    )
    (net (code "61") (name "C65_ROW7") (class "Default")
      (node (ref "SV2") (pin "5") (pinfunction "P5_5") (pintype "passive"))
      (node (ref "U1") (pin "68") (pinfunction "PE7_68") (pintype "bidirectional"))
    )
    (net (code "62") (name "C65_ROW8") (class "Default")
      (node (ref "SV2") (pin "2") (pinfunction "P2_2") (pintype "passive"))
      (node (ref "U1") (pin "69") (pinfunction "PE8_69") (pintype "bidirectional"))
    )
    (net (code "63") (name "COL0") (class "Default")
      (node (ref "SV1") (pin "13") (pinfunction "13_13") (pintype "passive"))
      (node (ref "U1") (pin "96") (pinfunction "PD8_96") (pintype "bidirectional"))
    )
    (net (code "64") (name "COL1") (class "Default")
      (node (ref "SV1") (pin "19") (pinfunction "19_19") (pintype "passive"))
      (node (ref "U1") (pin "97") (pinfunction "PD9_97") (pintype "bidirectional"))
    )
    (net (code "65") (name "COL2") (class "Default")
      (node (ref "SV1") (pin "18") (pinfunction "18_18") (pintype "passive"))
      (node (ref "U1") (pin "98") (pinfunction "PD10_98") (pintype "bidirectional"))
    )
    (net (code "66") (name "COL3") (class "Default")
      (node (ref "SV1") (pin "17") (pinfunction "17_17") (pintype "passive"))
      (node (ref "U1") (pin "99") (pinfunction "PD11_99") (pintype "bidirectional"))
    )
    (net (code "67") (name "COL4") (class "Default")
      (node (ref "SV1") (pin "16") (pinfunction "16_16") (pintype "passive"))
      (node (ref "U1") (pin "100") (pinfunction "PD12_100") (pintype "bidirectional"))
    )
    (net (code "68") (name "COL5") (class "Default")
      (node (ref "SV1") (pin "15") (pinfunction "15_15") (pintype "passive"))
      (node (ref "U1") (pin "101") (pinfunction "PD13_101") (pintype "bidirectional"))
    )
    (net (code "69") (name "COL6") (class "Default")
      (node (ref "SV1") (pin "14") (pinfunction "14_14") (pintype "passive"))
      (node (ref "U1") (pin "104") (pinfunction "PD14_104") (pintype "bidirectional"))
    )
    (net (code "70") (name "COL7") (class "Default")
      (node (ref "SV1") (pin "20") (pinfunction "20_20") (pintype "passive"))
      (node (ref "U1") (pin "105") (pinfunction "PD15_105") (pintype "bidirectional"))
    )
    (net (code "71") (name "FDD_LED") (class "Default")
      (node (ref "R6") (pin "1") (pinfunction "1_1") (pintype "passive"))
      (node (ref "U1") (pin "162") (pinfunction "PB4_162") (pintype "bidirectional"))
    )
    (net (code "72") (name "FLOPPY_LED") (class "Default")
      (node (ref "R6") (pin "2") (pinfunction "2_2") (pintype "passive"))
      (node (ref "SV2") (pin "25") (pinfunction "P25_25") (pintype "passive"))
    )
    (net (code "73") (name "GND") (class "Default")
      (node (ref "C1") (pin "2") (pinfunction "2_2") (pintype "passive"))
      (node (ref "C10") (pin "2") (pinfunction "2_2") (pintype "passive"))
      (node (ref "C11") (pin "2") (pinfunction "2_2") (pintype "passive"))
      (node (ref "C12") (pin "2") (pinfunction "2_2") (pintype "passive"))
      (node (ref "C13") (pin "2") (pinfunction "2_2") (pintype "passive"))
      (node (ref "C14") (pin "2") (pinfunction "2_2") (pintype "passive"))
      (node (ref "C15") (pin "2") (pinfunction "2_2") (pintype "passive"))
      (node (ref "C16") (pin "2") (pinfunction "2_2") (pintype "passive"))
      (node (ref "C17") (pin "2") (pinfunction "2_2") (pintype "passive"))
      (node (ref "C18") (pin "2") (pinfunction "2_2") (pintype "passive"))
      (node (ref "C19") (pin "1") (pinfunction "1_1") (pintype "passive"))
      (node (ref "C2") (pin "2") (pinfunction "2_2") (pintype "passive"))
      (node (ref "C20") (pin "1") (pinfunction "1_1") (pintype "passive"))
      (node (ref "C21") (pin "2") (pinfunction "2_2") (pintype "passive"))
      (node (ref "C22") (pin "2") (pinfunction "2_2") (pintype "passive"))
      (node (ref "C23") (pin "2") (pinfunction "2_2") (pintype "passive"))
      (node (ref "C24") (pin "2") (pinfunction "2_2") (pintype "passive"))
      (node (ref "C25") (pin "2") (pinfunction "2_2") (pintype "passive"))
      (node (ref "C26") (pin "2") (pinfunction "2_2") (pintype "passive"))
      (node (ref "C27") (pin "2") (pinfunction "2_2") (pintype "passive"))
      (node (ref "C28") (pin "2") (pinfunction "2_2") (pintype "passive"))
      (node (ref "C29") (pin "2") (pinfunction "2_2") (pintype "passive"))
      (node (ref "C3") (pin "2") (pinfunction "2_2") (pintype "passive"))
      (node (ref "C30") (pin "2") (pinfunction "2_2") (pintype "passive"))
      (node (ref "C31") (pin "2") (pinfunction "2_2") (pintype "passive"))
      (node (ref "C32") (pin "2") (pinfunction "2_2") (pintype "passive"))
      (node (ref "C4") (pin "2") (pinfunction "2_2") (pintype "passive"))
      (node (ref "C5") (pin "2") (pinfunction "2_2") (pintype "passive"))
      (node (ref "C6") (pin "2") (pinfunction "2_2") (pintype "passive"))
      (node (ref "C7") (pin "2") (pinfunction "2_2") (pintype "passive"))
      (node (ref "C8") (pin "2") (pinfunction "2_2") (pintype "passive"))
      (node (ref "C9") (pin "2") (pinfunction "2_2") (pintype "passive"))
      (node (ref "G1") (pin "-") (pinfunction "-_-") (pintype "passive"))
      (node (ref "J2") (pin "1") (pinfunction "1_1") (pintype "passive"))
      (node (ref "J2") (pin "2") (pinfunction "2_2") (pintype "passive"))
      (node (ref "JP1") (pin "2") (pinfunction "2_2") (pintype "passive"))
      (node (ref "R30") (pin "1") (pinfunction "1_1") (pintype "passive"))
      (node (ref "R31") (pin "1") (pinfunction "1_1") (pintype "passive"))
      (node (ref "R38") (pin "1") (pinfunction "1_1") (pintype "passive"))
      (node (ref "S1") (pin "B1") (pinfunction "B_B1") (pintype "passive"))
      (node (ref "SV1") (pin "1") (pinfunction "1_1") (pintype "passive"))
      (node (ref "SV2") (pin "1") (pinfunction "P1_1") (pintype "passive"))
      (node (ref "SV3") (pin "1") (pinfunction "1_1") (pintype "passive"))
      (node (ref "SV3") (pin "22") (pinfunction "22_22") (pintype "passive"))
      (node (ref "SV3") (pin "A") (pinfunction "A_A") (pintype "passive"))
      (node (ref "SV3") (pin "Z") (pinfunction "Z_Z") (pintype "passive"))
      (node (ref "SV4") (pin "3") (pinfunction "3_3") (pintype "passive"))
      (node (ref "SV5") (pin "10") (pinfunction "10_10") (pintype "passive"))
      (node (ref "SV5") (pin "9") (pinfunction "9_9") (pintype "passive"))
      (node (ref "SV6") (pin "10") (pinfunction "10_10") (pintype "passive"))
      (node (ref "SV6") (pin "9") (pinfunction "9_9") (pintype "passive"))
      (node (ref "SV7") (pin "10") (pinfunction "10_10") (pintype "passive"))
      (node (ref "SV7") (pin "9") (pinfunction "9_9") (pintype "passive"))
      (node (ref "SV8") (pin "4") (pinfunction "GND_4") (pintype "passive"))
      (node (ref "SV8") (pin "G1") (pinfunction "G1_G1") (pintype "passive"))
      (node (ref "SV9") (pin "1") (pinfunction "1_1") (pintype "passive"))
      (node (ref "SV9") (pin "2") (pinfunction "2_2") (pintype "passive"))
      (node (ref "SW1") (pin "1") (pinfunction "O_1") (pintype "passive"))
      (node (ref "SW1") (pin "3") (pinfunction "B_3") (pintype "passive"))
      (node (ref "SW1") (pin "4") (pinfunction "B1_4") (pintype "passive"))
      (node (ref "U1") (pin "102") (pinfunction "VSS_7_102") (pintype "power_in"))
      (node (ref "U1") (pin "113") (pinfunction "VSS_3_113") (pintype "power_in"))
      (node (ref "U1") (pin "126") (pinfunction "VSS_4_126") (pintype "power_in"))
      (node (ref "U1") (pin "135") (pinfunction "VSS_2_135") (pintype "power_in"))
      (node (ref "U1") (pin "14") (pinfunction "VSS_2_14") (pintype "power_in"))
      (node (ref "U1") (pin "148") (pinfunction "VSS_6_148") (pintype "power_in"))
      (node (ref "U1") (pin "158") (pinfunction "VSS_158") (pintype "power_in"))
      (node (ref "U1") (pin "22") (pinfunction "VSS_4_22") (pintype "power_in"))
      (node (ref "U1") (pin "37") (pinfunction "VSSA_37") (pintype "power_in"))
      (node (ref "U1") (pin "61") (pinfunction "VSS_61") (pintype "power_in"))
      (node (ref "U1") (pin "71") (pinfunction "VSS_3_71") (pintype "power_in"))
      (node (ref "U1") (pin "90") (pinfunction "VSS_5_90") (pintype "power_in"))
      (node (ref "U2") (pin "11") (pinfunction "GND_11") (pintype "power_in"))
      (node (ref "U2") (pin "12") (pinfunction "GND1_12") (pintype "power_in"))
      (node (ref "U2") (pin "13") (pinfunction "GND2_13") (pintype "power_in"))
      (node (ref "U2") (pin "22") (pinfunction "OE_22") (pintype "input"))
      (node (ref "U3") (pin "11") (pinfunction "GND_11") (pintype "power_in"))
      (node (ref "U3") (pin "12") (pinfunction "GND1_12") (pintype "power_in"))
      (node (ref "U3") (pin "13") (pinfunction "GND2_13") (pintype "power_in"))
      (node (ref "U3") (pin "22") (pinfunction "OE_22") (pintype "input"))
      (node (ref "U4") (pin "11") (pinfunction "GND_11") (pintype "power_in"))
      (node (ref "U4") (pin "12") (pinfunction "GND1_12") (pintype "power_in"))
      (node (ref "U4") (pin "13") (pinfunction "GND2_13") (pintype "power_in"))
      (node (ref "U4") (pin "22") (pinfunction "OE_22") (pintype "input"))
      (node (ref "X3") (pin "8") (pinfunction "M_8") (pintype "passive"))
      (node (ref "X4") (pin "1") (pinfunction "KL_1") (pintype "passive"))
      (node (ref "X5") (pin "8") (pinfunction "M_8") (pintype "passive"))
    )
    (net (code "74") (name "J1_BUTTON") (class "Default")
      (node (ref "R27") (pin "2") (pinfunction "2_2") (pintype "passive"))
      (node (ref "U1") (pin "141") (pinfunction "PC12_141") (pintype "bidirectional"))
      (node (ref "X3") (pin "6") (pinfunction "M_6") (pintype "passive"))
    )
    (net (code "75") (name "J1_DOWN") (class "Default")
      (node (ref "R23") (pin "2") (pinfunction "2_2") (pintype "passive"))
      (node (ref "U1") (pin "55") (pinfunction "PC5_55") (pintype "bidirectional"))
      (node (ref "X3") (pin "2") (pinfunction "M_2") (pintype "passive"))
    )
    (net (code "76") (name "J1_LEFT") (class "Default")
      (node (ref "R24") (pin "2") (pinfunction "2_2") (pintype "passive"))
      (node (ref "U1") (pin "115") (pinfunction "PC6_115") (pintype "bidirectional"))
      (node (ref "X3") (pin "3") (pinfunction "M_3") (pintype "passive"))
    )
    (net (code "77") (name "J1_RIGHT") (class "Default")
      (node (ref "R25") (pin "2") (pinfunction "2_2") (pintype "passive"))
      (node (ref "U1") (pin "116") (pinfunction "PC7_116") (pintype "bidirectional"))
      (node (ref "X3") (pin "4") (pinfunction "M_4") (pintype "passive"))
    )
    (net (code "78") (name "J1_UP") (class "Default")
      (node (ref "R1") (pin "2") (pinfunction "2_2") (pintype "passive"))
      (node (ref "U1") (pin "54") (pinfunction "PC4_54") (pintype "passive"))
      (node (ref "X3") (pin "1") (pinfunction "M_1") (pintype "passive"))
    )
    (net (code "79") (name "J2_BUTTON") (class "Default")
      (node (ref "R22") (pin "2") (pinfunction "2_2") (pintype "passive"))
      (node (ref "U1") (pin "8") (pinfunction "PC13_8") (pintype "passive"))
      (node (ref "X5") (pin "6") (pinfunction "M_6") (pintype "passive"))
    )
    (net (code "80") (name "J2_DOWN") (class "Default")
      (node (ref "R7") (pin "2") (pinfunction "2_2") (pintype "passive"))
      (node (ref "U1") (pin "117") (pinfunction "PC8_117") (pintype "bidirectional"))
      (node (ref "X5") (pin "2") (pinfunction "M_2") (pintype "passive"))
    )
    (net (code "81") (name "J2_LEFT") (class "Default")
      (node (ref "R8") (pin "2") (pinfunction "2_2") (pintype "passive"))
      (node (ref "U1") (pin "139") (pinfunction "PC10_139") (pintype "bidirectional"))
      (node (ref "X5") (pin "3") (pinfunction "M_3") (pintype "passive"))
    )
    (net (code "82") (name "J2_RIGHT") (class "Default")
      (node (ref "R9") (pin "2") (pinfunction "2_2") (pintype "passive"))
      (node (ref "U1") (pin "140") (pinfunction "PC11_140") (pintype "bidirectional"))
      (node (ref "X5") (pin "4") (pinfunction "M_4") (pintype "passive"))
    )
    (net (code "83") (name "J2_UP") (class "Default")
      (node (ref "R2") (pin "2") (pinfunction "2_2") (pintype "passive"))
      (node (ref "U1") (pin "118") (pinfunction "PC9_118") (pintype "bidirectional"))
      (node (ref "X5") (pin "1") (pinfunction "M_1") (pintype "passive"))
    )
    (net (code "84") (name "JA1") (class "Default")
      (node (ref "SV6") (pin "2") (pinfunction "2_2") (pintype "passive"))
      (node (ref "U1") (pin "66") (pinfunction "PG0_66") (pintype "bidirectional"))
    )
    (net (code "85") (name "JA2") (class "Default")
      (node (ref "SV6") (pin "4") (pinfunction "4_4") (pintype "passive"))
      (node (ref "U1") (pin "67") (pinfunction "PG1_67") (pintype "bidirectional"))
    )
    (net (code "86") (name "JA3") (class "Default")
      (node (ref "SV6") (pin "6") (pinfunction "6_6") (pintype "passive"))
      (node (ref "U1") (pin "106") (pinfunction "PG2_106") (pintype "bidirectional"))
    )
    (net (code "87") (name "JA4") (class "Default")
      (node (ref "SV6") (pin "8") (pinfunction "8_8") (pintype "passive"))
      (node (ref "U1") (pin "107") (pinfunction "PG3_107") (pintype "bidirectional"))
    )
    (net (code "88") (name "JA7") (class "Default")
      (node (ref "SV6") (pin "1") (pinfunction "1_1") (pintype "passive"))
      (node (ref "U1") (pin "108") (pinfunction "PG4_108") (pintype "bidirectional"))
    )
    (net (code "89") (name "JA8") (class "Default")
      (node (ref "SV6") (pin "3") (pinfunction "3_3") (pintype "passive"))
      (node (ref "U1") (pin "109") (pinfunction "PG5_109") (pintype "bidirectional"))
    )
    (net (code "90") (name "JA9") (class "Default")
      (node (ref "SV6") (pin "5") (pinfunction "5_5") (pintype "passive"))
      (node (ref "U1") (pin "110") (pinfunction "PG6_110") (pintype "bidirectional"))
    )
    (net (code "91") (name "JA10") (class "Default")
      (node (ref "SV6") (pin "7") (pinfunction "7_7") (pintype "passive"))
      (node (ref "U1") (pin "111") (pinfunction "PG7_111") (pintype "bidirectional"))
    )
    (net (code "92") (name "JB1") (class "Default")
      (node (ref "SV5") (pin "2") (pinfunction "2_2") (pintype "passive"))
      (node (ref "U1") (pin "112") (pinfunction "PG8_112") (pintype "bidirectional"))
    )
    (net (code "93") (name "JB2") (class "Default")
      (node (ref "SV5") (pin "4") (pinfunction "4_4") (pintype "passive"))
      (node (ref "U1") (pin "152") (pinfunction "PG9_152") (pintype "bidirectional"))
    )
    (net (code "94") (name "JB3") (class "Default")
      (node (ref "SV5") (pin "6") (pinfunction "6_6") (pintype "passive"))
      (node (ref "U1") (pin "153") (pinfunction "PG10_153") (pintype "bidirectional"))
    )
    (net (code "95") (name "JB4") (class "Default")
      (node (ref "SV5") (pin "8") (pinfunction "8_8") (pintype "passive"))
      (node (ref "U1") (pin "154") (pinfunction "PG11_154") (pintype "bidirectional"))
    )
    (net (code "96") (name "JB7") (class "Default")
      (node (ref "SV5") (pin "1") (pinfunction "1_1") (pintype "passive"))
      (node (ref "U1") (pin "155") (pinfunction "PG12_155") (pintype "bidirectional"))
    )
    (net (code "97") (name "JB8") (class "Default")
      (node (ref "SV5") (pin "3") (pinfunction "3_3") (pintype "passive"))
      (node (ref "U1") (pin "156") (pinfunction "PG13_156") (pintype "bidirectional"))
    )
    (net (code "98") (name "JB9") (class "Default")
      (node (ref "SV5") (pin "5") (pinfunction "5_5") (pintype "passive"))
      (node (ref "U1") (pin "157") (pinfunction "PG14_157") (pintype "bidirectional"))
    )
    (net (code "99") (name "JB10") (class "Default")
      (node (ref "SV5") (pin "7") (pinfunction "7_7") (pintype "passive"))
      (node (ref "U1") (pin "160") (pinfunction "PG15_160") (pintype "bidirectional"))
    )
    (net (code "100") (name "NRST") (class "Default")
      (node (ref "C31") (pin "1") (pinfunction "1_1") (pintype "passive"))
      (node (ref "JP1") (pin "1") (pinfunction "1_1") (pintype "passive"))
      (node (ref "R35") (pin "1") (pinfunction "1_1") (pintype "passive"))
      (node (ref "R36") (pin "1") (pinfunction "1_1") (pintype "passive"))
      (node (ref "U1") (pin "31") (pinfunction "NRST_31") (pintype "passive"))
    )
    (net (code "101") (name "Net-(C22-Pad1)") (class "Default")
      (node (ref "C22") (pin "1") (pinfunction "1_1") (pintype "passive"))
      (node (ref "Q1") (pin "1") (pinfunction "1_1") (pintype "passive"))
      (node (ref "R4") (pin "2") (pinfunction "2_2") (pintype "passive"))
    )
    (net (code "102") (name "Net-(R32-Pad1)") (class "Default")
      (node (ref "R32") (pin "1") (pinfunction "1_1") (pintype "passive"))
      (node (ref "SV4") (pin "1") (pinfunction "1_1") (pintype "passive"))
    )
    (net (code "103") (name "Net-(R33-Pad2)") (class "Default")
      (node (ref "R33") (pin "2") (pinfunction "2_2") (pintype "passive"))
      (node (ref "SV4") (pin "2") (pinfunction "2_2") (pintype "passive"))
    )
    (net (code "104") (name "Net-(R34-Pad2)") (class "Default")
      (node (ref "R34") (pin "2") (pinfunction "2_2") (pintype "passive"))
      (node (ref "SV4") (pin "4") (pinfunction "4_4") (pintype "passive"))
    )
    (net (code "105") (name "Net-(R35-Pad2)") (class "Default")
      (node (ref "R35") (pin "2") (pinfunction "2_2") (pintype "passive"))
      (node (ref "SV4") (pin "5") (pinfunction "5_5") (pintype "passive"))
    )
    (net (code "106") (name "Net-(S1-P)") (class "Default")
      (node (ref "J2") (pin "3") (pinfunction "3_3") (pintype "passive"))
      (node (ref "S1") (pin "2") (pinfunction "P_2") (pintype "passive"))
    )
    (net (code "107") (name "Net-(U1A-BYPASS_REG)") (class "Default")
      (node (ref "R38") (pin "2") (pinfunction "2_2") (pintype "passive"))
      (node (ref "U1") (pin "48") (pinfunction "BYPASS_REG_48") (pintype "passive"))
    )
    (net (code "108") (name "Net-(U1A-PH0)") (class "Default")
      (node (ref "R4") (pin "1") (pinfunction "1_1") (pintype "passive"))
      (node (ref "U1") (pin "29") (pinfunction "PH0_29") (pintype "passive"))
    )
    (net (code "109") (name "Net-(U1A-PH1)") (class "Default")
      (node (ref "C21") (pin "1") (pinfunction "1_1") (pintype "passive"))
      (node (ref "Q1") (pin "2") (pinfunction "2_2") (pintype "passive"))
      (node (ref "U1") (pin "30") (pinfunction "PH1_30") (pintype "passive"))
    )
    (net (code "110") (name "Net-(U1A-VBAT)") (class "Default")
      (node (ref "G1") (pin "+") (pinfunction "+_+") (pintype "passive"))
      (node (ref "U1") (pin "6") (pinfunction "VBAT_6") (pintype "passive"))
    )
    (net (code "111") (name "Net-(U1A-VCAP_1)") (class "Default")
      (node (ref "C30") (pin "1") (pinfunction "1_1") (pintype "passive"))
      (node (ref "U1") (pin "81") (pinfunction "VCAP_1_81") (pintype "passive"))
    )
    (net (code "112") (name "Net-(U1A-VDDA)") (class "Default")
      (node (ref "C19") (pin "2") (pinfunction "2_2") (pintype "passive"))
      (node (ref "C20") (pin "2") (pinfunction "2_2") (pintype "passive"))
      (node (ref "L1") (pin "1") (pinfunction "1_1") (pintype "passive"))
      (node (ref "R3") (pin "1") (pinfunction "1_1") (pintype "passive"))
      (node (ref "U1") (pin "36") (pinfunction "VDDA_2_36") (pintype "power_in"))
      (node (ref "U1") (pin "39") (pinfunction "VDDA_39") (pintype "power_in"))
    )
    (net (code "113") (name "Net-(U1A-VREF+)") (class "Default")
      (node (ref "C17") (pin "1") (pinfunction "1_1") (pintype "passive"))
      (node (ref "C18") (pin "1") (pinfunction "1_1") (pintype "passive"))
      (node (ref "R3") (pin "2") (pinfunction "2_2") (pintype "passive"))
      (node (ref "U1") (pin "38") (pinfunction "VREF+_38") (pintype "passive"))
    )
    (net (code "114") (name "Net-(U1B-PDR_ON)") (class "Default")
      (node (ref "R39") (pin "1") (pinfunction "1_1") (pintype "passive"))
      (node (ref "U1") (pin "171") (pinfunction "PDR_ON_171") (pintype "passive"))
    )
    (net (code "115") (name "Net-(U1B-VCAP_2)") (class "Default")
      (node (ref "C29") (pin "1") (pinfunction "1_1") (pintype "passive"))
      (node (ref "U1") (pin "125") (pinfunction "VCAP_2_125") (pintype "passive"))
    )
    (net (code "116") (name "Net-(X3G-M)") (class "Default")
      (node (ref "R26") (pin "2") (pinfunction "2_2") (pintype "passive"))
      (node (ref "X3") (pin "7") (pinfunction "M_7") (pintype "passive"))
    )
    (net (code "117") (name "Net-(X5G-M)") (class "Default")
      (node (ref "R21") (pin "2") (pinfunction "2_2") (pintype "passive"))
      (node (ref "X5") (pin "7") (pinfunction "M_7") (pintype "passive"))
    )
    (net (code "118") (name "PA7") (class "Default")
      (node (ref "SV9") (pin "3") (pinfunction "3_3") (pintype "passive"))
      (node (ref "U1") (pin "53") (pinfunction "PA7_53") (pintype "passive"))
    )
    (net (code "119") (name "PA8") (class "Default")
      (node (ref "SV9") (pin "4") (pinfunction "4_4") (pintype "passive"))
      (node (ref "U1") (pin "119") (pinfunction "PA8_119") (pintype "bidirectional"))
    )
    (net (code "120") (name "PA9") (class "Default")
      (node (ref "SV9") (pin "5") (pinfunction "5_5") (pintype "passive"))
      (node (ref "U1") (pin "120") (pinfunction "PA9_120") (pintype "bidirectional"))
    )
    (net (code "121") (name "PA10") (class "Default")
      (node (ref "SV9") (pin "6") (pinfunction "6_6") (pintype "passive"))
      (node (ref "U1") (pin "121") (pinfunction "PA10_121") (pintype "bidirectional"))
    )
    (net (code "122") (name "PA13") (class "Default")
      (node (ref "R34") (pin "1") (pinfunction "1_1") (pintype "passive"))
      (node (ref "U1") (pin "124") (pinfunction "PA13_124") (pintype "bidirectional"))
    )
    (net (code "123") (name "PA14") (class "Default")
      (node (ref "R33") (pin "1") (pinfunction "1_1") (pintype "passive"))
      (node (ref "U1") (pin "137") (pinfunction "PA14_137") (pintype "bidirectional"))
    )
    (net (code "124") (name "PA15") (class "Default")
      (node (ref "SV9") (pin "7") (pinfunction "7_7") (pintype "passive"))
      (node (ref "U1") (pin "138") (pinfunction "PA15_138") (pintype "bidirectional"))
    )
    (net (code "125") (name "PB6") (class "Default")
      (node (ref "SV9") (pin "8") (pinfunction "8_8") (pintype "passive"))
      (node (ref "U1") (pin "164") (pinfunction "PB6_164") (pintype "bidirectional"))
    )
    (net (code "126") (name "PB7") (class "Default")
      (node (ref "SV9") (pin "9") (pinfunction "9_9") (pintype "passive"))
      (node (ref "U1") (pin "165") (pinfunction "PB7_165") (pintype "bidirectional"))
    )
    (net (code "127") (name "PH2") (class "Default")
      (node (ref "SV9") (pin "14") (pinfunction "14_14") (pintype "passive"))
    )
    (net (code "128") (name "PH3") (class "Default")
      (node (ref "SV9") (pin "15") (pinfunction "15_15") (pintype "passive"))
      (node (ref "U1") (pin "44") (pinfunction "PH3_44") (pintype "passive"))
    )
    (net (code "129") (name "PI8") (class "Default")
      (node (ref "SV9") (pin "10") (pinfunction "10_10") (pintype "passive"))
      (node (ref "U1") (pin "7") (pinfunction "PI8_7") (pintype "passive"))
    )
    (net (code "130") (name "PI9") (class "Default")
      (node (ref "SV9") (pin "11") (pinfunction "11_11") (pintype "passive"))
      (node (ref "U1") (pin "11") (pinfunction "PI9_11") (pintype "passive"))
    )
    (net (code "131") (name "PI10") (class "Default")
      (node (ref "SV9") (pin "12") (pinfunction "12_12") (pintype "passive"))
      (node (ref "U1") (pin "12") (pinfunction "PI10_12") (pintype "passive"))
    )
    (net (code "132") (name "PI11") (class "Default")
      (node (ref "SV9") (pin "13") (pinfunction "13_13") (pintype "passive"))
      (node (ref "U1") (pin "13") (pinfunction "PI11_13") (pintype "passive"))
    )
    (net (code "133") (name "POT1_X") (class "Default")
      (node (ref "U1") (pin "41") (pinfunction "PA1_41") (pintype "passive"))
      (node (ref "X3") (pin "9") (pinfunction "M_9") (pintype "passive"))
    )
    (net (code "134") (name "POT1_Y") (class "Default")
      (node (ref "U1") (pin "40") (pinfunction "PA0_40") (pintype "passive"))
      (node (ref "X3") (pin "5") (pinfunction "M_5") (pintype "passive"))
    )
    (net (code "135") (name "POT2_X") (class "Default")
      (node (ref "U1") (pin "47") (pinfunction "PA3_47") (pintype "passive"))
      (node (ref "X5") (pin "9") (pinfunction "M_9") (pintype "passive"))
    )
    (net (code "136") (name "POT2_Y") (class "Default")
      (node (ref "U1") (pin "42") (pinfunction "PA2_42") (pintype "passive"))
      (node (ref "X5") (pin "5") (pinfunction "M_5") (pintype "passive"))
    )
    (net (code "137") (name "POWER_LED") (class "Default")
      (node (ref "R5") (pin "2") (pinfunction "2_2") (pintype "passive"))
      (node (ref "SV2") (pin "24") (pinfunction "P24_24") (pintype "passive"))
    )
    (net (code "138") (name "PWR_LED") (class "Default")
      (node (ref "R5") (pin "1") (pinfunction "1_1") (pintype "passive"))
      (node (ref "U1") (pin "163") (pinfunction "PB5_163") (pintype "bidirectional"))
    )
    (net (code "139") (name "RESET") (class "Default")
      (node (ref "C32") (pin "1") (pinfunction "1_1") (pintype "passive"))
      (node (ref "R37") (pin "2") (pinfunction "2_2") (pintype "passive"))
      (node (ref "SW1") (pin "2") (pinfunction "P_2") (pintype "passive"))
      (node (ref "U1") (pin "43") (pinfunction "PH2_43") (pintype "passive"))
    )
    (net (code "140") (name "ROW0") (class "Default")
      (node (ref "SV1") (pin "12") (pinfunction "12_12") (pintype "passive"))
      (node (ref "U1") (pin "142") (pinfunction "PD0_142") (pintype "bidirectional"))
    )
    (net (code "141") (name "ROW1") (class "Default")
      (node (ref "SV1") (pin "11") (pinfunction "11_11") (pintype "passive"))
      (node (ref "U1") (pin "143") (pinfunction "PD1_143") (pintype "bidirectional"))
    )
    (net (code "142") (name "ROW2") (class "Default")
      (node (ref "SV1") (pin "10") (pinfunction "10_10") (pintype "passive"))
      (node (ref "U1") (pin "144") (pinfunction "PD2_144") (pintype "bidirectional"))
    )
    (net (code "143") (name "ROW3") (class "Default")
      (node (ref "SV1") (pin "5") (pinfunction "5_5") (pintype "passive"))
      (node (ref "U1") (pin "145") (pinfunction "PD3_145") (pintype "bidirectional"))
    )
    (net (code "144") (name "ROW4") (class "Default")
      (node (ref "SV1") (pin "8") (pinfunction "8_8") (pintype "passive"))
      (node (ref "U1") (pin "146") (pinfunction "PD4_146") (pintype "bidirectional"))
    )
    (net (code "145") (name "ROW5") (class "Default")
      (node (ref "SV1") (pin "7") (pinfunction "7_7") (pintype "passive"))
      (node (ref "U1") (pin "147") (pinfunction "PD5_147") (pintype "bidirectional"))
    )
    (net (code "146") (name "ROW6") (class "Default")
      (node (ref "SV1") (pin "6") (pinfunction "6_6") (pintype "passive"))
      (node (ref "U1") (pin "150") (pinfunction "PD6_150") (pintype "bidirectional"))
    )
    (net (code "147") (name "ROW7") (class "Default")
      (node (ref "SV1") (pin "9") (pinfunction "9_9") (pintype "passive"))
      (node (ref "U1") (pin "151") (pinfunction "PD7_151") (pintype "bidirectional"))
    )
    (net (code "148") (name "ST_A0") (class "Default")
      (node (ref "U1") (pin "16") (pinfunction "PF0_16") (pintype "passive"))
      (node (ref "U2") (pin "21") (pinfunction "B1_21") (pintype "bidirectional"))
    )
    (net (code "149") (name "ST_A1") (class "Default")
      (node (ref "U1") (pin "17") (pinfunction "PF1_17") (pintype "passive"))
      (node (ref "U2") (pin "20") (pinfunction "B2_20") (pintype "bidirectional"))
    )
    (net (code "150") (name "ST_A2") (class "Default")
      (node (ref "U1") (pin "18") (pinfunction "PF2_18") (pintype "passive"))
      (node (ref "U2") (pin "19") (pinfunction "B3_19") (pintype "bidirectional"))
    )
    (net (code "151") (name "ST_A3") (class "Default")
      (node (ref "U1") (pin "19") (pinfunction "PF3_19") (pintype "passive"))
      (node (ref "U2") (pin "18") (pinfunction "B4_18") (pintype "bidirectional"))
    )
    (net (code "152") (name "ST_A4") (class "Default")
      (node (ref "U1") (pin "20") (pinfunction "PF4_20") (pintype "passive"))
      (node (ref "U2") (pin "17") (pinfunction "B5_17") (pintype "bidirectional"))
    )
    (net (code "153") (name "ST_A5") (class "Default")
      (node (ref "U1") (pin "21") (pinfunction "PF5_21") (pintype "passive"))
      (node (ref "U2") (pin "16") (pinfunction "B6_16") (pintype "bidirectional"))
    )
    (net (code "154") (name "ST_A6") (class "Default")
      (node (ref "U1") (pin "24") (pinfunction "PF6_24") (pintype "passive"))
      (node (ref "U2") (pin "15") (pinfunction "B7_15") (pintype "bidirectional"))
    )
    (net (code "155") (name "ST_A7") (class "Default")
      (node (ref "U1") (pin "25") (pinfunction "PF7_25") (pintype "passive"))
      (node (ref "U2") (pin "14") (pinfunction "B8_14") (pintype "bidirectional"))
    )
    (net (code "156") (name "ST_A8") (class "Default")
      (node (ref "U1") (pin "26") (pinfunction "PF8_26") (pintype "passive"))
      (node (ref "U3") (pin "21") (pinfunction "B1_21") (pintype "bidirectional"))
    )
    (net (code "157") (name "ST_A9") (class "Default")
      (node (ref "U1") (pin "27") (pinfunction "PF9_27") (pintype "passive"))
      (node (ref "U3") (pin "20") (pinfunction "B2_20") (pintype "bidirectional"))
    )
    (net (code "158") (name "ST_A10") (class "Default")
      (node (ref "U1") (pin "28") (pinfunction "PF10_28") (pintype "passive"))
      (node (ref "U3") (pin "19") (pinfunction "B3_19") (pintype "bidirectional"))
    )
    (net (code "159") (name "ST_A11") (class "Default")
      (node (ref "U1") (pin "59") (pinfunction "PF11_59") (pintype "bidirectional"))
      (node (ref "U3") (pin "18") (pinfunction "B4_18") (pintype "bidirectional"))
    )
    (net (code "160") (name "ST_A12") (class "Default")
      (node (ref "U1") (pin "60") (pinfunction "PF12_60") (pintype "bidirectional"))
      (node (ref "U3") (pin "17") (pinfunction "B5_17") (pintype "bidirectional"))
    )
    (net (code "161") (name "ST_A13") (class "Default")
      (node (ref "U1") (pin "63") (pinfunction "PF13_63") (pintype "bidirectional"))
      (node (ref "U3") (pin "16") (pinfunction "B6_16") (pintype "bidirectional"))
    )
    (net (code "162") (name "ST_A14") (class "Default")
      (node (ref "U1") (pin "64") (pinfunction "PF14_64") (pintype "bidirectional"))
      (node (ref "U3") (pin "15") (pinfunction "B7_15") (pintype "bidirectional"))
    )
    (net (code "163") (name "ST_A15") (class "Default")
      (node (ref "U1") (pin "65") (pinfunction "PF15_65") (pintype "bidirectional"))
      (node (ref "U3") (pin "14") (pinfunction "B8_14") (pintype "bidirectional"))
    )
    (net (code "164") (name "ST_D0") (class "Default")
      (node (ref "U1") (pin "131") (pinfunction "PI0_131") (pintype "bidirectional"))
      (node (ref "U4") (pin "21") (pinfunction "B1_21") (pintype "bidirectional"))
    )
    (net (code "165") (name "ST_D1") (class "Default")
      (node (ref "U1") (pin "132") (pinfunction "PI1_132") (pintype "bidirectional"))
      (node (ref "U4") (pin "20") (pinfunction "B2_20") (pintype "bidirectional"))
    )
    (net (code "166") (name "ST_D2") (class "Default")
      (node (ref "U1") (pin "133") (pinfunction "PI2_133") (pintype "bidirectional"))
      (node (ref "U4") (pin "19") (pinfunction "B3_19") (pintype "bidirectional"))
    )
    (net (code "167") (name "ST_D3") (class "Default")
      (node (ref "U1") (pin "134") (pinfunction "PI3_134") (pintype "bidirectional"))
      (node (ref "U4") (pin "18") (pinfunction "B4_18") (pintype "bidirectional"))
    )
    (net (code "168") (name "ST_D4") (class "Default")
      (node (ref "U1") (pin "173") (pinfunction "PI4_173") (pintype "bidirectional"))
      (node (ref "U4") (pin "17") (pinfunction "B5_17") (pintype "bidirectional"))
    )
    (net (code "169") (name "ST_D5") (class "Default")
      (node (ref "U1") (pin "174") (pinfunction "PI5_174") (pintype "bidirectional"))
      (node (ref "U4") (pin "16") (pinfunction "B6_16") (pintype "bidirectional"))
    )
    (net (code "170") (name "ST_D6") (class "Default")
      (node (ref "U1") (pin "175") (pinfunction "PI6_175") (pintype "bidirectional"))
      (node (ref "U4") (pin "15") (pinfunction "B7_15") (pintype "bidirectional"))
    )
    (net (code "171") (name "ST_D7") (class "Default")
      (node (ref "U1") (pin "176") (pinfunction "PI7_176") (pintype "bidirectional"))
      (node (ref "U4") (pin "14") (pinfunction "B8_14") (pintype "bidirectional"))
    )
    (net (code "172") (name "USB_D_N") (class "Default")
      (node (ref "SV8") (pin "2") (pinfunction "DM_2") (pintype "passive"))
      (node (ref "U1") (pin "122") (pinfunction "PA11_122") (pintype "bidirectional"))
    )
    (net (code "173") (name "USB_D_P") (class "Default")
      (node (ref "SV8") (pin "3") (pinfunction "DP_3") (pintype "passive"))
      (node (ref "U1") (pin "123") (pinfunction "PA12_123") (pintype "bidirectional"))
    )
    (net (code "174") (name "VCC") (class "Default")
      (node (ref "C23") (pin "1") (pinfunction "1_1") (pintype "passive"))
      (node (ref "C24") (pin "1") (pinfunction "1_1") (pintype "passive"))
      (node (ref "C25") (pin "1") (pinfunction "1_1") (pintype "passive"))
      (node (ref "R10") (pin "1") (pinfunction "1_1") (pintype "passive"))
      (node (ref "R11") (pin "1") (pinfunction "1_1") (pintype "passive"))
      (node (ref "R12") (pin "1") (pinfunction "1_1") (pintype "passive"))
      (node (ref "R13") (pin "1") (pinfunction "1_1") (pintype "passive"))
      (node (ref "R14") (pin "1") (pinfunction "1_1") (pintype "passive"))
      (node (ref "R15") (pin "1") (pinfunction "1_1") (pintype "passive"))
      (node (ref "R16") (pin "1") (pinfunction "1_1") (pintype "passive"))
      (node (ref "R17") (pin "1") (pinfunction "1_1") (pintype "passive"))
      (node (ref "R18") (pin "1") (pinfunction "1_1") (pintype "passive"))
      (node (ref "R19") (pin "1") (pinfunction "1_1") (pintype "passive"))
      (node (ref "R20") (pin "1") (pinfunction "1_1") (pintype "passive"))
      (node (ref "S1") (pin "3") (pinfunction "S_3") (pintype "passive"))
      (node (ref "SV3") (pin "2") (pinfunction "2_2") (pintype "passive"))
      (node (ref "SV3") (pin "3") (pinfunction "3_3") (pintype "passive"))
      (node (ref "SV9") (pin "17") (pinfunction "17_17") (pintype "passive"))
      (node (ref "SV9") (pin "18") (pinfunction "18_18") (pintype "passive"))
      (node (ref "U2") (pin "1") (pinfunction "VCCA_1") (pintype "power_in"))
      (node (ref "U3") (pin "1") (pinfunction "VCCA_1") (pintype "power_in"))
      (node (ref "U4") (pin "1") (pinfunction "VCCA_1") (pintype "power_in"))
      (node (ref "X4") (pin "3") (pinfunction "KL_3") (pintype "passive"))
    )
    (net (code "175") (name "XADC1_N") (class "Default")
      (node (ref "SV7") (pin "1") (pinfunction "1_1") (pintype "passive"))
      (node (ref "U1") (pin "167") (pinfunction "PB8_167") (pintype "bidirectional"))
    )
    (net (code "176") (name "XADC1_P") (class "Default")
      (node (ref "SV7") (pin "2") (pinfunction "2_2") (pintype "passive"))
      (node (ref "U1") (pin "168") (pinfunction "PB9_168") (pintype "bidirectional"))
    )
    (net (code "177") (name "XADC2_N") (class "Default")
      (node (ref "SV7") (pin "3") (pinfunction "3_3") (pintype "passive"))
      (node (ref "U1") (pin "79") (pinfunction "PB10_79") (pintype "bidirectional"))
    )
    (net (code "178") (name "XADC2_P") (class "Default")
      (node (ref "SV7") (pin "4") (pinfunction "4_4") (pintype "passive"))
      (node (ref "U1") (pin "80") (pinfunction "PB11_80") (pintype "bidirectional"))
    )
    (net (code "179") (name "XADC3_N") (class "Default")
      (node (ref "SV7") (pin "5") (pinfunction "5_5") (pintype "passive"))
      (node (ref "U1") (pin "92") (pinfunction "PB12_92") (pintype "bidirectional"))
    )
    (net (code "180") (name "XADC3_P") (class "Default")
      (node (ref "SV7") (pin "6") (pinfunction "6_6") (pintype "passive"))
      (node (ref "U1") (pin "93") (pinfunction "PB13_93") (pintype "bidirectional"))
    )
    (net (code "181") (name "XADC4_N") (class "Default")
      (node (ref "SV7") (pin "7") (pinfunction "7_7") (pintype "passive"))
      (node (ref "U1") (pin "94") (pinfunction "PB14_94") (pintype "bidirectional"))
    )
    (net (code "182") (name "XADC4_P") (class "Default")
      (node (ref "SV7") (pin "8") (pinfunction "8_8") (pintype "passive"))
      (node (ref "U1") (pin "95") (pinfunction "PB15_95") (pintype "bidirectional"))
    )
    (net (code "183") (name "unconnected-(G1-+-Pad+@1)") (class "Default")
      (node (ref "G1") (pin "+@1") (pinfunction "+_+@1") (pintype "passive"))
    )
    (net (code "184") (name "unconnected-(S1-O-Pad1)") (class "Default")
      (node (ref "S1") (pin "1") (pinfunction "O_1") (pintype "passive"))
    )
    (net (code "185") (name "unconnected-(SV1-Pad2)") (class "Default")
      (node (ref "SV1") (pin "2") (pinfunction "2_2") (pintype "passive"))
    )
    (net (code "186") (name "unconnected-(SV4-Pad6)") (class "Default")
      (node (ref "SV4") (pin "6") (pinfunction "6_6") (pintype "passive"))
    )
    (net (code "187") (name "unconnected-(SV8-PadG2)") (class "Default")
      (node (ref "SV8") (pin "G2") (pinfunction "G2_G2") (pintype "passive"))
    )
    (net (code "188") (name "unconnected-(SV8-VCC-Pad1)") (class "Default")
      (node (ref "SV8") (pin "1") (pinfunction "VCC_1") (pintype "passive"))
    )
    (net (code "189") (name "unconnected-(SV9-Pad16)") (class "Default")
      (node (ref "SV9") (pin "16") (pinfunction "16_16") (pintype "passive"))
    )
    (net (code "190") (name "unconnected-(U1A-PH4-Pad45)") (class "Default")
      (node (ref "U1") (pin "45") (pinfunction "PH4_45") (pintype "passive"))
    )
    (net (code "191") (name "{slash}REST") (class "Default")
      (node (ref "SV1") (pin "3") (pinfunction "3_3") (pintype "passive"))
      (node (ref "U1") (pin "9") (pinfunction "PC14_9") (pintype "passive"))
    )
    (net (code "192") (name "{slash}R_W_A0-7") (class "Default")
      (node (ref "U1") (pin "56") (pinfunction "PB0_56") (pintype "bidirectional"))
      (node (ref "U2") (pin "2") (pinfunction "DIR_2") (pintype "input"))
    )
    (net (code "193") (name "{slash}R_W_A8-15") (class "Default")
      (node (ref "U1") (pin "57") (pinfunction "PB1_57") (pintype "bidirectional"))
      (node (ref "U3") (pin "2") (pinfunction "DIR_2") (pintype "input"))
    )
    (net (code "194") (name "{slash}R_W_D0-D7") (class "Default")
      (node (ref "U1") (pin "161") (pinfunction "PB3_161") (pintype "bidirectional"))
      (node (ref "U4") (pin "2") (pinfunction "DIR_2") (pintype "input"))
    )
  )
)
